# space_invaders_board.net
KiCad netlist of a schematic drawn in EAGLE
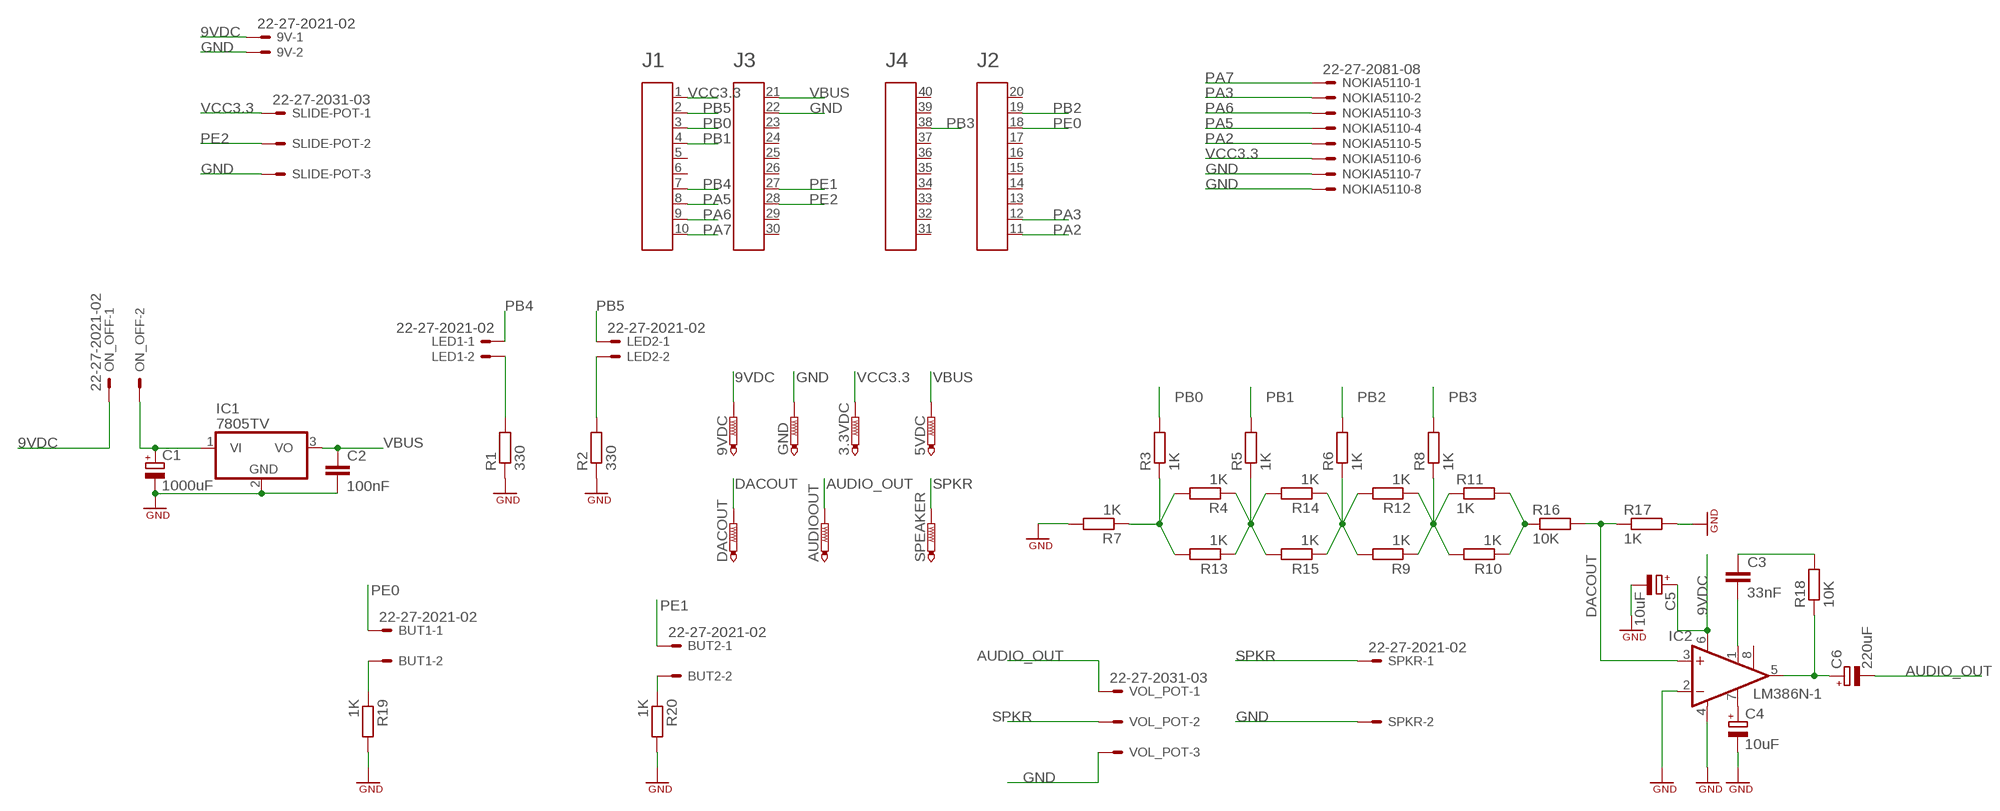
[diagram p0: schematic, sheet 1]

(export (version "E")
  (design (tool "Eeschema 10.0.6"))
  (components
    (comp (ref "3.3VDC")
      (value "PTR1PAD1-13")
      (footprint "eagle-import:P1-13")
      (libsource (lib "eagle-import") (part "PTR1PAD1-13"))
    )
    (comp (ref "5VDC")
      (value "PTR1PAD1-13")
      (footprint "eagle-import:P1-13")
      (libsource (lib "eagle-import") (part "PTR1PAD1-13"))
    )
    (comp (ref "9V")
      (value "22-27-2021-02")
      (footprint "eagle-import:6410-02")
      (libsource (lib "eagle-import") (part "22-?-0227-2021"))
    )
    (comp (ref "9VDC")
      (value "PTR1PAD1-13")
      (footprint "eagle-import:P1-13")
      (libsource (lib "eagle-import") (part "PTR1PAD1-13"))
    )
    (comp (ref "AUDIOOUT")
      (value "PTR1PAD1-13")
      (footprint "eagle-import:P1-13")
      (libsource (lib "eagle-import") (part "PTR1PAD1-13"))
    )
    (comp (ref "BUT1")
      (value "22-27-2021-02")
      (footprint "eagle-import:6410-02")
      (libsource (lib "eagle-import") (part "22-?-0227-2021"))
    )
    (comp (ref "BUT2")
      (value "22-27-2021-02")
      (footprint "eagle-import:6410-02")
      (libsource (lib "eagle-import") (part "22-?-0227-2021"))
    )
    (comp (ref "C1")
      (value "1000uF")
      (footprint "eagle-import:E5-10,5")
      (libsource (lib "eagle-import") (part "resistor_CPOL-EUE5-10.5"))
    )
    (comp (ref "C2")
      (value "100nF")
      (footprint "eagle-import:C025-025X050")
      (libsource (lib "eagle-import") (part "C-EU025-025X050"))
    )
    (comp (ref "C3")
      (value "33nF")
      (footprint "eagle-import:C2.5-3")
      (libsource (lib "eagle-import") (part "C2,5-3"))
    )
    (comp (ref "C4")
      (value "10uF")
      (footprint "eagle-import:E2,5-6E")
      (libsource (lib "eagle-import") (part "CPOL-EUE2,5-6E"))
    )
    (comp (ref "C5")
      (value "10uF")
      (footprint "eagle-import:E2,5-6E")
      (libsource (lib "eagle-import") (part "CPOL-EUE2,5-6E"))
    )
    (comp (ref "C6")
      (value "220uF")
      (footprint "eagle-import:E2,5-7")
      (libsource (lib "eagle-import") (part "CPOL-EUE2.5-7"))
    )
    (comp (ref "DACOUT")
      (value "PTR1PAD1-13")
      (footprint "eagle-import:P1-13")
      (libsource (lib "eagle-import") (part "PTR1PAD1-13"))
    )
    (comp (ref "GND")
      (value "PTR1PAD1-13")
      (footprint "eagle-import:P1-13")
      (libsource (lib "eagle-import") (part "PTR1PAD1-13"))
    )
    (comp (ref "IC1")
      (value "7805TV")
      (footprint "eagle-import:TO220V")
      (libsource (lib "eagle-import") (part "78TV05"))
    )
    (comp (ref "IC2")
      (value "LM386N-1")
      (footprint "eagle-import:DIL08")
      (libsource (lib "eagle-import") (part "LM386?-N1"))
    )
    (comp (ref "LED1")
      (value "22-27-2021-02")
      (footprint "eagle-import:6410-02")
      (libsource (lib "eagle-import") (part "22-?-0227-2021"))
    )
    (comp (ref "LED2")
      (value "22-27-2021-02")
      (footprint "eagle-import:6410-02")
      (libsource (lib "eagle-import") (part "22-?-0227-2021"))
    )
    (comp (ref "NOKIA5110")
      (value "22-27-2081-08")
      (footprint "eagle-import:6410-08")
      (libsource (lib "eagle-import") (part "22-?-0827-2081"))
    )
    (comp (ref "ON_OFF")
      (value "22-27-2021-02")
      (footprint "eagle-import:6410-02")
      (libsource (lib "eagle-import") (part "22-?-0227-2021"))
    )
    (comp (ref "R1")
      (value "330")
      (footprint "eagle-import:0207_15")
      (libsource (lib "eagle-import") (part "resistor_R-EU_0207/15"))
    )
    (comp (ref "R2")
      (value "330")
      (footprint "eagle-import:0207_15")
      (libsource (lib "eagle-import") (part "resistor_R-EU_0207/15"))
    )
    (comp (ref "R3")
      (value "1K")
      (footprint "eagle-import:0207_15")
      (libsource (lib "eagle-import") (part "resistor_R-EU_0207/15"))
    )
    (comp (ref "R4")
      (value "1K")
      (footprint "eagle-import:0207_15")
      (libsource (lib "eagle-import") (part "resistor_R-EU_0207/15"))
    )
    (comp (ref "R5")
      (value "1K")
      (footprint "eagle-import:0207_15")
      (libsource (lib "eagle-import") (part "resistor_R-EU_0207/15"))
    )
    (comp (ref "R6")
      (value "1K")
      (footprint "eagle-import:0207_15")
      (libsource (lib "eagle-import") (part "resistor_R-EU_0207/15"))
    )
    (comp (ref "R7")
      (value "1K")
      (footprint "eagle-import:0207_15")
      (libsource (lib "eagle-import") (part "resistor_R-EU_0207/15"))
    )
    (comp (ref "R8")
      (value "1K")
      (footprint "eagle-import:0207_15")
      (libsource (lib "eagle-import") (part "resistor_R-EU_0207/15"))
    )
    (comp (ref "R9")
      (value "1K")
      (footprint "eagle-import:0207_15")
      (libsource (lib "eagle-import") (part "resistor_R-EU_0207/15"))
    )
    (comp (ref "R10")
      (value "1K")
      (footprint "eagle-import:0207_15")
      (libsource (lib "eagle-import") (part "resistor_R-EU_0207/15"))
    )
    (comp (ref "R11")
      (value "1K")
      (footprint "eagle-import:0207_15")
      (libsource (lib "eagle-import") (part "resistor_R-EU_0207/15"))
    )
    (comp (ref "R12")
      (value "1K")
      (footprint "eagle-import:0207_15")
      (libsource (lib "eagle-import") (part "resistor_R-EU_0207/15"))
    )
    (comp (ref "R13")
      (value "1K")
      (footprint "eagle-import:0207_15")
      (libsource (lib "eagle-import") (part "resistor_R-EU_0207/15"))
    )
    (comp (ref "R14")
      (value "1K")
      (footprint "eagle-import:0207_15")
      (libsource (lib "eagle-import") (part "resistor_R-EU_0207/15"))
    )
    (comp (ref "R15")
      (value "1K")
      (footprint "eagle-import:0207_15")
      (libsource (lib "eagle-import") (part "resistor_R-EU_0207/15"))
    )
    (comp (ref "R16")
      (value "10K")
      (footprint "eagle-import:0207_15")
      (libsource (lib "eagle-import") (part "resistor_R-EU_0207/15"))
    )
    (comp (ref "R17")
      (value "1K")
      (footprint "eagle-import:0207_15")
      (libsource (lib "eagle-import") (part "resistor_R-EU_0207/15"))
    )
    (comp (ref "R18")
      (value "10K")
      (footprint "eagle-import:0207_15")
      (libsource (lib "eagle-import") (part "R-EU_0207/15"))
    )
    (comp (ref "R19")
      (value "1K")
      (footprint "eagle-import:0207_15")
      (libsource (lib "eagle-import") (part "resistor_R-EU_0207/15"))
    )
    (comp (ref "R20")
      (value "1K")
      (footprint "eagle-import:0207_15")
      (libsource (lib "eagle-import") (part "resistor_R-EU_0207/15"))
    )
    (comp (ref "SLIDE-POT")
      (value "22-27-2031-03")
      (footprint "eagle-import:6410-03")
      (libsource (lib "eagle-import") (part "22-?-0327-2031"))
    )
    (comp (ref "SPEAKER")
      (value "PTR1PAD1-13")
      (footprint "eagle-import:P1-13")
      (libsource (lib "eagle-import") (part "PTR1PAD1-13"))
    )
    (comp (ref "SPKR")
      (value "22-27-2021-02")
      (footprint "eagle-import:6410-02")
      (libsource (lib "eagle-import") (part "22-?-0227-2021"))
    )
    (comp (ref "TIVAC_HEADER")
      (value "0")
      (footprint "eagle-import:4X10-BOOSTERPACK")
      (libsource (lib "eagle-import") (part "HEADER4X10-BOOSTERPACK"))
    )
    (comp (ref "VOL_POT")
      (value "22-27-2031-03")
      (footprint "eagle-import:6410-03")
      (libsource (lib "eagle-import") (part "22-?-0327-2031"))
    )
  )
  (nets
    (net (code "1") (name "/9VDC") (class "Default")
      (node (ref "9V") (pin "1") (pinfunction "S_1") (pintype "passive"))
      (node (ref "9VDC") (pin "TP") (pinfunction "TP_TP") (pintype "input"))
      (node (ref "C5") (pin "+") (pinfunction "+_+") (pintype "passive"))
      (node (ref "IC2") (pin "6") (pinfunction "VS_6") (pintype "power_in"))
      (node (ref "ON_OFF") (pin "1") (pinfunction "S_1") (pintype "passive"))
    )
    (net (code "2") (name "/AUDIO_OUT") (class "Default")
      (node (ref "AUDIOOUT") (pin "TP") (pinfunction "TP_TP") (pintype "input"))
      (node (ref "C6") (pin "-") (pinfunction "-_-") (pintype "passive"))
      (node (ref "VOL_POT") (pin "1") (pinfunction "S_1") (pintype "passive"))
    )
    (net (code "3") (name "/DACOUT") (class "Default")
      (node (ref "DACOUT") (pin "TP") (pinfunction "TP_TP") (pintype "input"))
      (node (ref "IC2") (pin "3") (pinfunction "+IN_3") (pintype "input"))
      (node (ref "R16") (pin "2") (pinfunction "2_2") (pintype "passive"))
      (node (ref "R17") (pin "1") (pinfunction "1_1") (pintype "passive"))
    )
    (net (code "4") (name "/PA2") (class "Default")
      (node (ref "NOKIA5110") (pin "5") (pinfunction "S_5") (pintype "passive"))
      (node (ref "TIVAC_HEADER") (pin "11") (pinfunction "P$11_11") (pintype "bidirectional"))
    )
    (net (code "5") (name "/PA3") (class "Default")
      (node (ref "NOKIA5110") (pin "2") (pinfunction "S_2") (pintype "passive"))
      (node (ref "TIVAC_HEADER") (pin "12") (pinfunction "P$12_12") (pintype "bidirectional"))
    )
    (net (code "6") (name "/PA5") (class "Default")
      (node (ref "NOKIA5110") (pin "4") (pinfunction "S_4") (pintype "passive"))
      (node (ref "TIVAC_HEADER") (pin "8") (pinfunction "P$8_8") (pintype "bidirectional"))
    )
    (net (code "7") (name "/PA6") (class "Default")
      (node (ref "NOKIA5110") (pin "3") (pinfunction "S_3") (pintype "passive"))
      (node (ref "TIVAC_HEADER") (pin "9") (pinfunction "P$9_9") (pintype "bidirectional"))
    )
    (net (code "8") (name "/PA7") (class "Default")
      (node (ref "NOKIA5110") (pin "1") (pinfunction "S_1") (pintype "passive"))
      (node (ref "TIVAC_HEADER") (pin "10") (pinfunction "P$10_10") (pintype "bidirectional"))
    )
    (net (code "9") (name "/PB0") (class "Default")
      (node (ref "R3") (pin "2") (pinfunction "2_2") (pintype "passive"))
      (node (ref "TIVAC_HEADER") (pin "3") (pinfunction "P$3_3") (pintype "bidirectional"))
    )
    (net (code "10") (name "/PB1") (class "Default")
      (node (ref "R5") (pin "2") (pinfunction "2_2") (pintype "passive"))
      (node (ref "TIVAC_HEADER") (pin "4") (pinfunction "P$4_4") (pintype "bidirectional"))
    )
    (net (code "11") (name "/PB2") (class "Default")
      (node (ref "R6") (pin "2") (pinfunction "2_2") (pintype "passive"))
      (node (ref "TIVAC_HEADER") (pin "19") (pinfunction "P$19_19") (pintype "bidirectional"))
    )
    (net (code "12") (name "/PB3") (class "Default")
      (node (ref "R8") (pin "2") (pinfunction "2_2") (pintype "passive"))
      (node (ref "TIVAC_HEADER") (pin "38") (pinfunction "P$38_38") (pintype "bidirectional"))
    )
    (net (code "13") (name "/PB4") (class "Default")
      (node (ref "LED1") (pin "1") (pinfunction "S_1") (pintype "passive"))
      (node (ref "TIVAC_HEADER") (pin "7") (pinfunction "P$7_7") (pintype "bidirectional"))
    )
    (net (code "14") (name "/PB5") (class "Default")
      (node (ref "LED2") (pin "1") (pinfunction "S_1") (pintype "passive"))
      (node (ref "TIVAC_HEADER") (pin "2") (pinfunction "P$2_2") (pintype "bidirectional"))
    )
    (net (code "15") (name "/PE0") (class "Default")
      (node (ref "BUT1") (pin "1") (pinfunction "S_1") (pintype "passive"))
      (node (ref "TIVAC_HEADER") (pin "18") (pinfunction "P$18_18") (pintype "bidirectional"))
    )
    (net (code "16") (name "/PE1") (class "Default")
      (node (ref "BUT2") (pin "1") (pinfunction "S_1") (pintype "passive"))
      (node (ref "TIVAC_HEADER") (pin "27") (pinfunction "P$27_27") (pintype "bidirectional"))
    )
    (net (code "17") (name "/PE2") (class "Default")
      (node (ref "SLIDE-POT") (pin "2") (pinfunction "S_2") (pintype "passive"))
      (node (ref "TIVAC_HEADER") (pin "28") (pinfunction "P$28_28") (pintype "bidirectional"))
    )
    (net (code "18") (name "/SPKR") (class "Default")
      (node (ref "SPEAKER") (pin "TP") (pinfunction "TP_TP") (pintype "input"))
      (node (ref "SPKR") (pin "1") (pinfunction "S_1") (pintype "passive"))
      (node (ref "VOL_POT") (pin "2") (pinfunction "S_2") (pintype "passive"))
    )
    (net (code "19") (name "/VBUS") (class "Default")
      (node (ref "5VDC") (pin "TP") (pinfunction "TP_TP") (pintype "input"))
      (node (ref "C2") (pin "1") (pinfunction "1_1") (pintype "passive"))
      (node (ref "IC1") (pin "3") (pinfunction "VO_3") (pintype "passive"))
      (node (ref "TIVAC_HEADER") (pin "21") (pinfunction "P$21_21") (pintype "bidirectional"))
    )
    (net (code "20") (name "/VCC3.3") (class "Default")
      (node (ref "3.3VDC") (pin "TP") (pinfunction "TP_TP") (pintype "input"))
      (node (ref "NOKIA5110") (pin "6") (pinfunction "S_6") (pintype "passive"))
      (node (ref "SLIDE-POT") (pin "1") (pinfunction "S_1") (pintype "passive"))
      (node (ref "TIVAC_HEADER") (pin "1") (pinfunction "P$1_1") (pintype "bidirectional"))
    )
    (net (code "21") (name "GND") (class "Default")
      (node (ref "9V") (pin "2") (pinfunction "S_2") (pintype "passive"))
      (node (ref "C1") (pin "-") (pinfunction "-_-") (pintype "passive"))
      (node (ref "C2") (pin "2") (pinfunction "2_2") (pintype "passive"))
      (node (ref "C4") (pin "-") (pinfunction "-_-") (pintype "passive"))
      (node (ref "C5") (pin "-") (pinfunction "-_-") (pintype "passive"))
      (node (ref "GND") (pin "TP") (pinfunction "TP_TP") (pintype "input"))
      (node (ref "IC1") (pin "2") (pinfunction "GND_2") (pintype "passive"))
      (node (ref "IC2") (pin "2") (pinfunction "-IN_2") (pintype "input"))
      (node (ref "IC2") (pin "4") (pinfunction "GND_4") (pintype "power_in"))
      (node (ref "NOKIA5110") (pin "7") (pinfunction "S_7") (pintype "passive"))
      (node (ref "NOKIA5110") (pin "8") (pinfunction "S_8") (pintype "passive"))
      (node (ref "R1") (pin "1") (pinfunction "1_1") (pintype "passive"))
      (node (ref "R17") (pin "2") (pinfunction "2_2") (pintype "passive"))
      (node (ref "R19") (pin "2") (pinfunction "2_2") (pintype "passive"))
      (node (ref "R2") (pin "1") (pinfunction "1_1") (pintype "passive"))
      (node (ref "R20") (pin "2") (pinfunction "2_2") (pintype "passive"))
      (node (ref "R7") (pin "2") (pinfunction "2_2") (pintype "passive"))
      (node (ref "SLIDE-POT") (pin "3") (pinfunction "S_3") (pintype "passive"))
      (node (ref "SPKR") (pin "2") (pinfunction "S_2") (pintype "passive"))
      (node (ref "TIVAC_HEADER") (pin "22") (pinfunction "P$22_22") (pintype "bidirectional"))
      (node (ref "VOL_POT") (pin "3") (pinfunction "S_3") (pintype "passive"))
    )
    (net (code "22") (name "Net-(BUT1B-S)") (class "Default")
      (node (ref "BUT1") (pin "2") (pinfunction "S_2") (pintype "passive"))
      (node (ref "R19") (pin "1") (pinfunction "1_1") (pintype "passive"))
    )
    (net (code "23") (name "Net-(BUT2B-S)") (class "Default")
      (node (ref "BUT2") (pin "2") (pinfunction "S_2") (pintype "passive"))
      (node (ref "R20") (pin "1") (pinfunction "1_1") (pintype "passive"))
    )
    (net (code "24") (name "Net-(C3-Pad1)") (class "Default")
      (node (ref "C3") (pin "1") (pinfunction "1_1") (pintype "passive"))
      (node (ref "R18") (pin "2") (pinfunction "2_2") (pintype "passive"))
    )
    (net (code "25") (name "Net-(C3-Pad2)") (class "Default")
      (node (ref "C3") (pin "2") (pinfunction "2_2") (pintype "passive"))
      (node (ref "IC2") (pin "1") (pinfunction "GAIN_1") (pintype "passive"))
    )
    (net (code "26") (name "Net-(IC1-VI)") (class "Default")
      (node (ref "C1") (pin "+") (pinfunction "+_+") (pintype "passive"))
      (node (ref "IC1") (pin "1") (pinfunction "VI_1") (pintype "input"))
      (node (ref "ON_OFF") (pin "2") (pinfunction "S_2") (pintype "passive"))
    )
    (net (code "27") (name "Net-(IC2-BYPASS)") (class "Default")
      (node (ref "C4") (pin "+") (pinfunction "+_+") (pintype "passive"))
      (node (ref "IC2") (pin "7") (pinfunction "BYPASS_7") (pintype "passive"))
    )
    (net (code "28") (name "Net-(IC2-OUT)") (class "Default")
      (node (ref "C6") (pin "+") (pinfunction "+_+") (pintype "passive"))
      (node (ref "IC2") (pin "5") (pinfunction "OUT_5") (pintype "output"))
      (node (ref "R18") (pin "1") (pinfunction "1_1") (pintype "passive"))
    )
    (net (code "29") (name "Net-(LED1B-S)") (class "Default")
      (node (ref "LED1") (pin "2") (pinfunction "S_2") (pintype "passive"))
      (node (ref "R1") (pin "2") (pinfunction "2_2") (pintype "passive"))
    )
    (net (code "30") (name "Net-(LED2B-S)") (class "Default")
      (node (ref "LED2") (pin "2") (pinfunction "S_2") (pintype "passive"))
      (node (ref "R2") (pin "2") (pinfunction "2_2") (pintype "passive"))
    )
    (net (code "31") (name "Net-(R10-Pad1)") (class "Default")
      (node (ref "R10") (pin "1") (pinfunction "1_1") (pintype "passive"))
      (node (ref "R11") (pin "2") (pinfunction "2_2") (pintype "passive"))
      (node (ref "R16") (pin "1") (pinfunction "1_1") (pintype "passive"))
    )
    (net (code "32") (name "Net-(R10-Pad2)") (class "Default")
      (node (ref "R10") (pin "2") (pinfunction "2_2") (pintype "passive"))
      (node (ref "R11") (pin "1") (pinfunction "1_1") (pintype "passive"))
      (node (ref "R12") (pin "1") (pinfunction "1_1") (pintype "passive"))
      (node (ref "R8") (pin "1") (pinfunction "1_1") (pintype "passive"))
      (node (ref "R9") (pin "1") (pinfunction "1_1") (pintype "passive"))
    )
    (net (code "33") (name "Net-(R12-Pad2)") (class "Default")
      (node (ref "R12") (pin "2") (pinfunction "2_2") (pintype "passive"))
      (node (ref "R14") (pin "1") (pinfunction "1_1") (pintype "passive"))
      (node (ref "R15") (pin "1") (pinfunction "1_1") (pintype "passive"))
      (node (ref "R6") (pin "1") (pinfunction "1_1") (pintype "passive"))
      (node (ref "R9") (pin "2") (pinfunction "2_2") (pintype "passive"))
    )
    (net (code "34") (name "Net-(R13-Pad1)") (class "Default")
      (node (ref "R13") (pin "1") (pinfunction "1_1") (pintype "passive"))
      (node (ref "R14") (pin "2") (pinfunction "2_2") (pintype "passive"))
      (node (ref "R15") (pin "2") (pinfunction "2_2") (pintype "passive"))
      (node (ref "R4") (pin "1") (pinfunction "1_1") (pintype "passive"))
      (node (ref "R5") (pin "1") (pinfunction "1_1") (pintype "passive"))
    )
    (net (code "35") (name "Net-(R13-Pad2)") (class "Default")
      (node (ref "R13") (pin "2") (pinfunction "2_2") (pintype "passive"))
      (node (ref "R3") (pin "1") (pinfunction "1_1") (pintype "passive"))
      (node (ref "R4") (pin "2") (pinfunction "2_2") (pintype "passive"))
      (node (ref "R7") (pin "1") (pinfunction "1_1") (pintype "passive"))
    )
    (net (code "36") (name "unconnected-(IC2-GAIN-Pad8)") (class "Default")
      (node (ref "IC2") (pin "8") (pinfunction "GAIN_8") (pintype "passive"))
    )
    (net (code "37") (name "unconnected-(TIVAC_HEADER-P$5-Pad5)") (class "Default")
      (node (ref "TIVAC_HEADER") (pin "5") (pinfunction "P$5_5") (pintype "bidirectional"))
    )
    (net (code "38") (name "unconnected-(TIVAC_HEADER-P$6-Pad6)") (class "Default")
      (node (ref "TIVAC_HEADER") (pin "6") (pinfunction "P$6_6") (pintype "bidirectional"))
    )
    (net (code "39") (name "unconnected-(TIVAC_HEADER-P$13-Pad13)") (class "Default")
      (node (ref "TIVAC_HEADER") (pin "13") (pinfunction "P$13_13") (pintype "bidirectional"))
    )
    (net (code "40") (name "unconnected-(TIVAC_HEADER-P$14-Pad14)") (class "Default")
      (node (ref "TIVAC_HEADER") (pin "14") (pinfunction "P$14_14") (pintype "bidirectional"))
    )
    (net (code "41") (name "unconnected-(TIVAC_HEADER-P$15-Pad15)") (class "Default")
      (node (ref "TIVAC_HEADER") (pin "15") (pinfunction "P$15_15") (pintype "bidirectional"))
    )
    (net (code "42") (name "unconnected-(TIVAC_HEADER-P$16-Pad16)") (class "Default")
      (node (ref "TIVAC_HEADER") (pin "16") (pinfunction "P$16_16") (pintype "bidirectional"))
    )
    (net (code "43") (name "unconnected-(TIVAC_HEADER-P$17-Pad17)") (class "Default")
      (node (ref "TIVAC_HEADER") (pin "17") (pinfunction "P$17_17") (pintype "bidirectional"))
    )
    (net (code "44") (name "unconnected-(TIVAC_HEADER-P$20-Pad20)") (class "Default")
      (node (ref "TIVAC_HEADER") (pin "20") (pinfunction "P$20_20") (pintype "bidirectional"))
    )
    (net (code "45") (name "unconnected-(TIVAC_HEADER-P$23-Pad23)") (class "Default")
      (node (ref "TIVAC_HEADER") (pin "23") (pinfunction "P$23_23") (pintype "bidirectional"))
    )
    (net (code "46") (name "unconnected-(TIVAC_HEADER-P$24-Pad24)") (class "Default")
      (node (ref "TIVAC_HEADER") (pin "24") (pinfunction "P$24_24") (pintype "bidirectional"))
    )
    (net (code "47") (name "unconnected-(TIVAC_HEADER-P$25-Pad25)") (class "Default")
      (node (ref "TIVAC_HEADER") (pin "25") (pinfunction "P$25_25") (pintype "bidirectional"))
    )
    (net (code "48") (name "unconnected-(TIVAC_HEADER-P$26-Pad26)") (class "Default")
      (node (ref "TIVAC_HEADER") (pin "26") (pinfunction "P$26_26") (pintype "bidirectional"))
    )
    (net (code "49") (name "unconnected-(TIVAC_HEADER-P$29-Pad29)") (class "Default")
      (node (ref "TIVAC_HEADER") (pin "29") (pinfunction "P$29_29") (pintype "bidirectional"))
    )
    (net (code "50") (name "unconnected-(TIVAC_HEADER-P$30-Pad30)") (class "Default")
      (node (ref "TIVAC_HEADER") (pin "30") (pinfunction "P$30_30") (pintype "bidirectional"))
    )
    (net (code "51") (name "unconnected-(TIVAC_HEADER-P$31-Pad31)") (class "Default")
      (node (ref "TIVAC_HEADER") (pin "31") (pinfunction "P$31_31") (pintype "bidirectional"))
    )
    (net (code "52") (name "unconnected-(TIVAC_HEADER-P$32-Pad32)") (class "Default")
      (node (ref "TIVAC_HEADER") (pin "32") (pinfunction "P$32_32") (pintype "bidirectional"))
    )
    (net (code "53") (name "unconnected-(TIVAC_HEADER-P$33-Pad33)") (class "Default")
      (node (ref "TIVAC_HEADER") (pin "33") (pinfunction "P$33_33") (pintype "bidirectional"))
    )
    (net (code "54") (name "unconnected-(TIVAC_HEADER-P$34-Pad34)") (class "Default")
      (node (ref "TIVAC_HEADER") (pin "34") (pinfunction "P$34_34") (pintype "bidirectional"))
    )
    (net (code "55") (name "unconnected-(TIVAC_HEADER-P$35-Pad35)") (class "Default")
      (node (ref "TIVAC_HEADER") (pin "35") (pinfunction "P$35_35") (pintype "bidirectional"))
    )
    (net (code "56") (name "unconnected-(TIVAC_HEADER-P$36-Pad36)") (class "Default")
      (node (ref "TIVAC_HEADER") (pin "36") (pinfunction "P$36_36") (pintype "bidirectional"))
    )
    (net (code "57") (name "unconnected-(TIVAC_HEADER-P$37-Pad37)") (class "Default")
      (node (ref "TIVAC_HEADER") (pin "37") (pinfunction "P$37_37") (pintype "bidirectional"))
    )
    (net (code "58") (name "unconnected-(TIVAC_HEADER-P$39-Pad39)") (class "Default")
      (node (ref "TIVAC_HEADER") (pin "39") (pinfunction "P$39_39") (pintype "bidirectional"))
    )
    (net (code "59") (name "unconnected-(TIVAC_HEADER-P$40-Pad40)") (class "Default")
      (node (ref "TIVAC_HEADER") (pin "40") (pinfunction "P$40_40") (pintype "bidirectional"))
    )
  )
)
